# Smart_Humidifier.net
KiCad netlist of a schematic drawn in Altium Designer
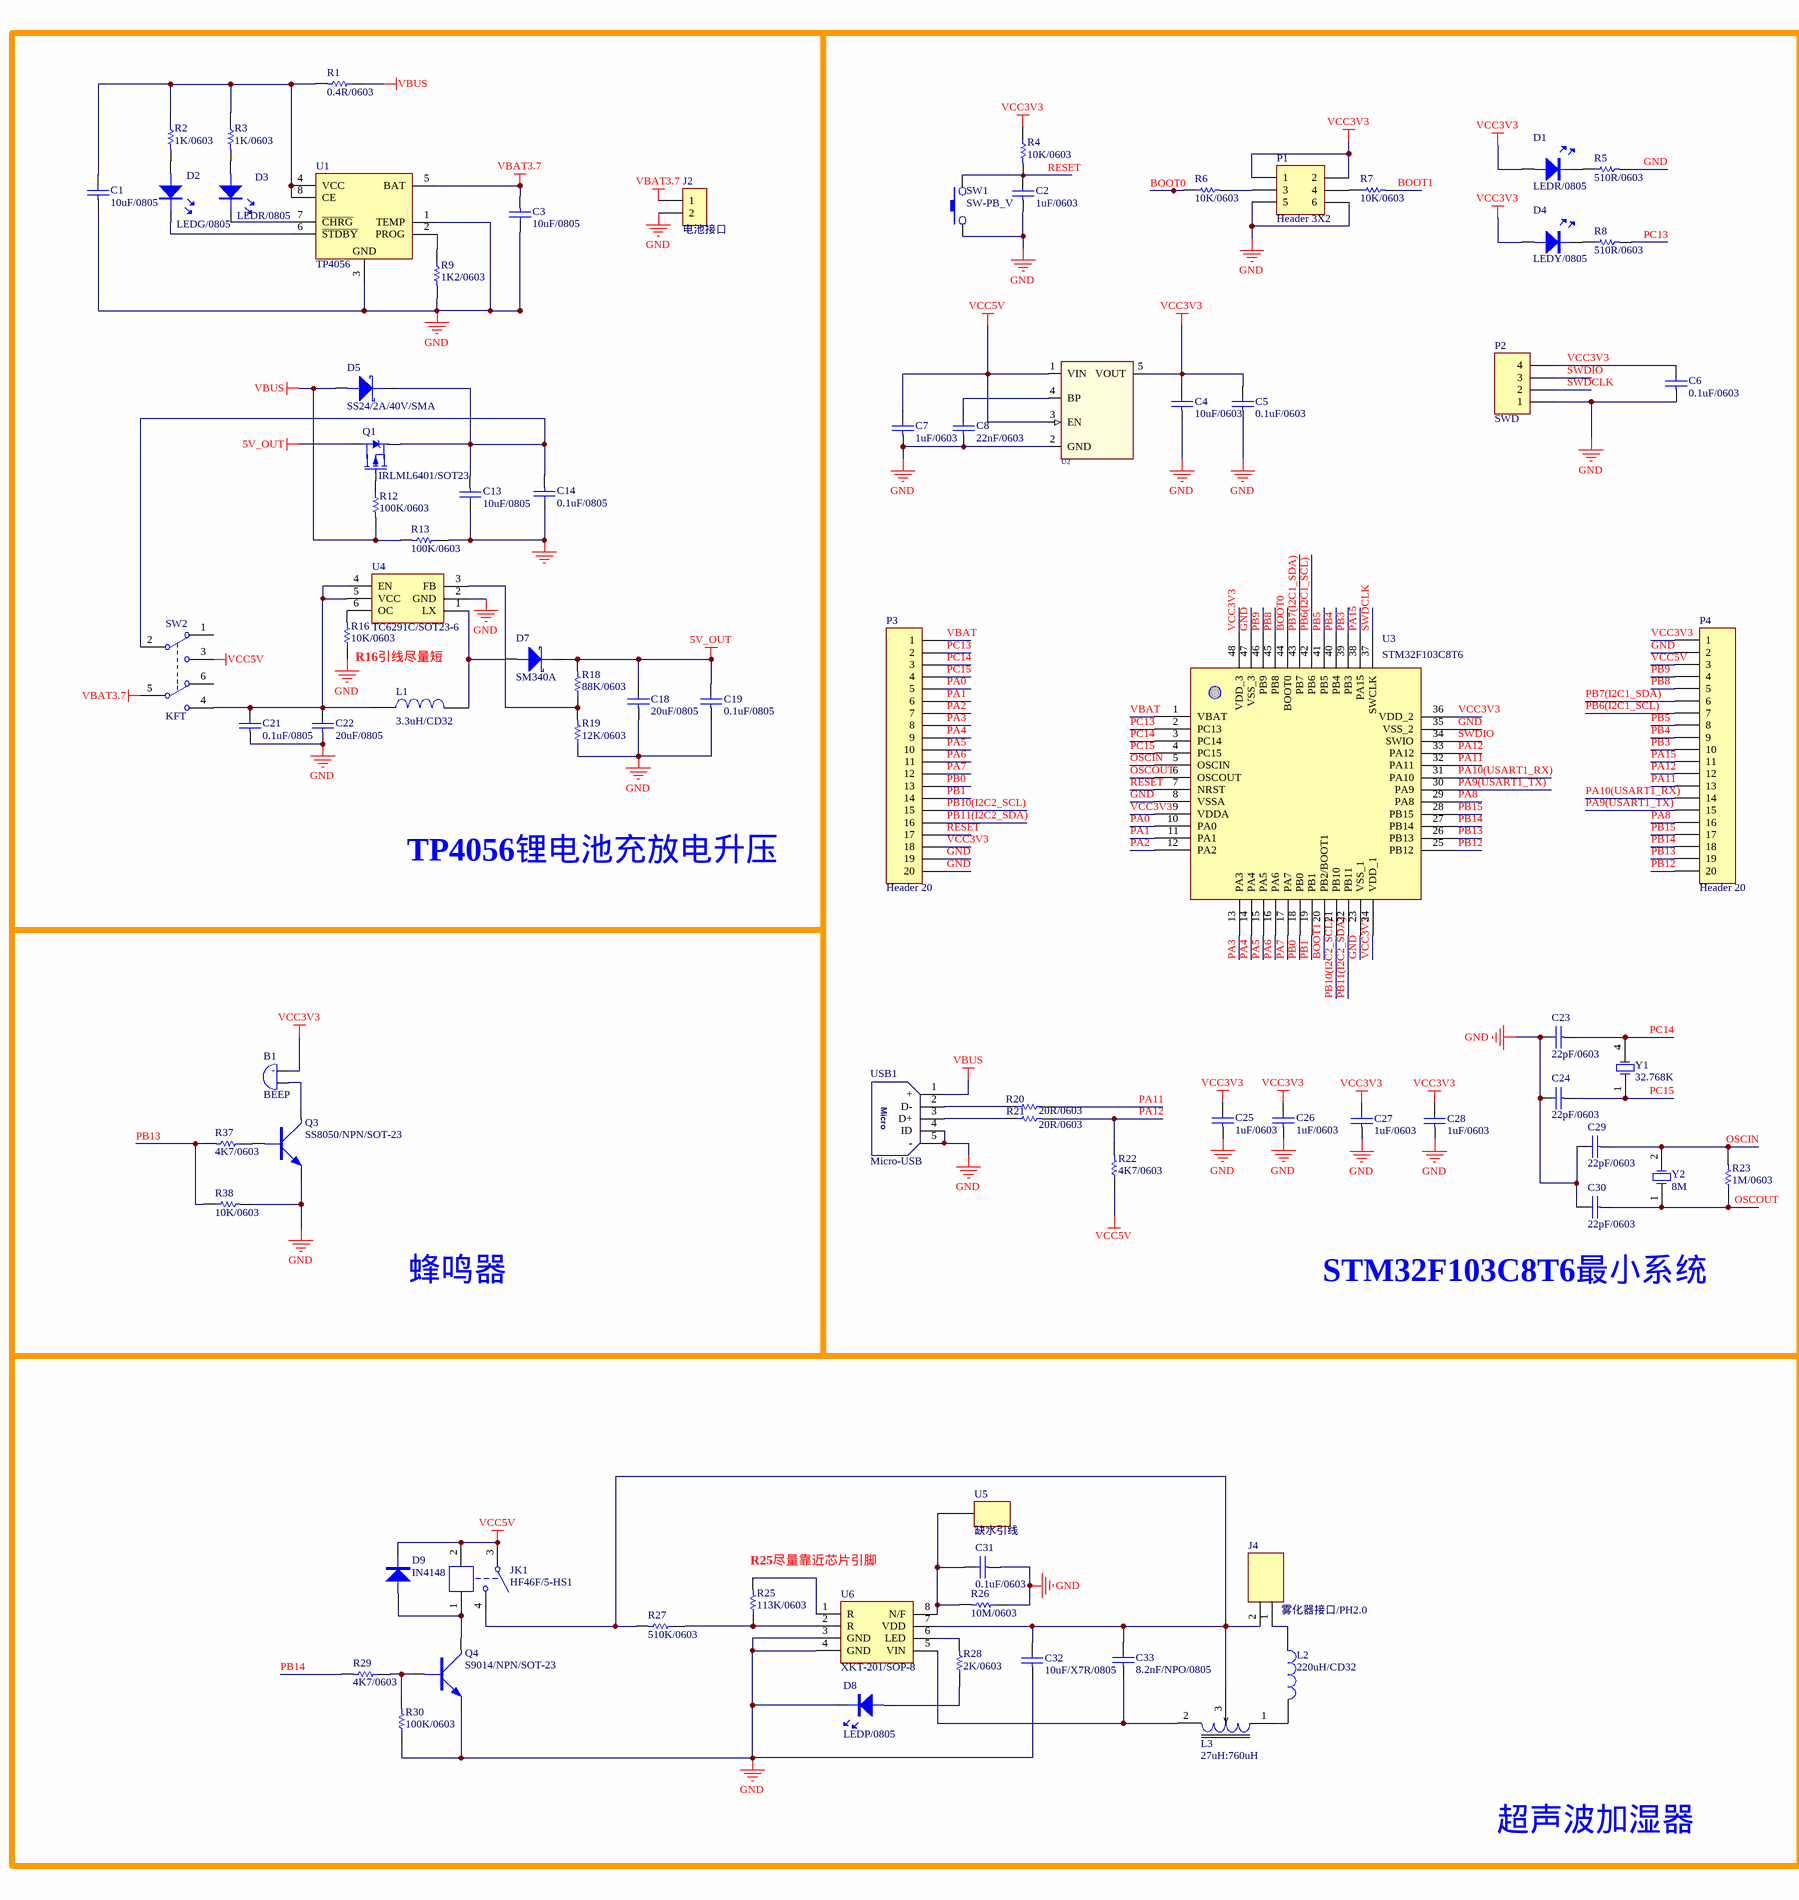
[diagram p0: Smart Humidifier.SchDoc, left]
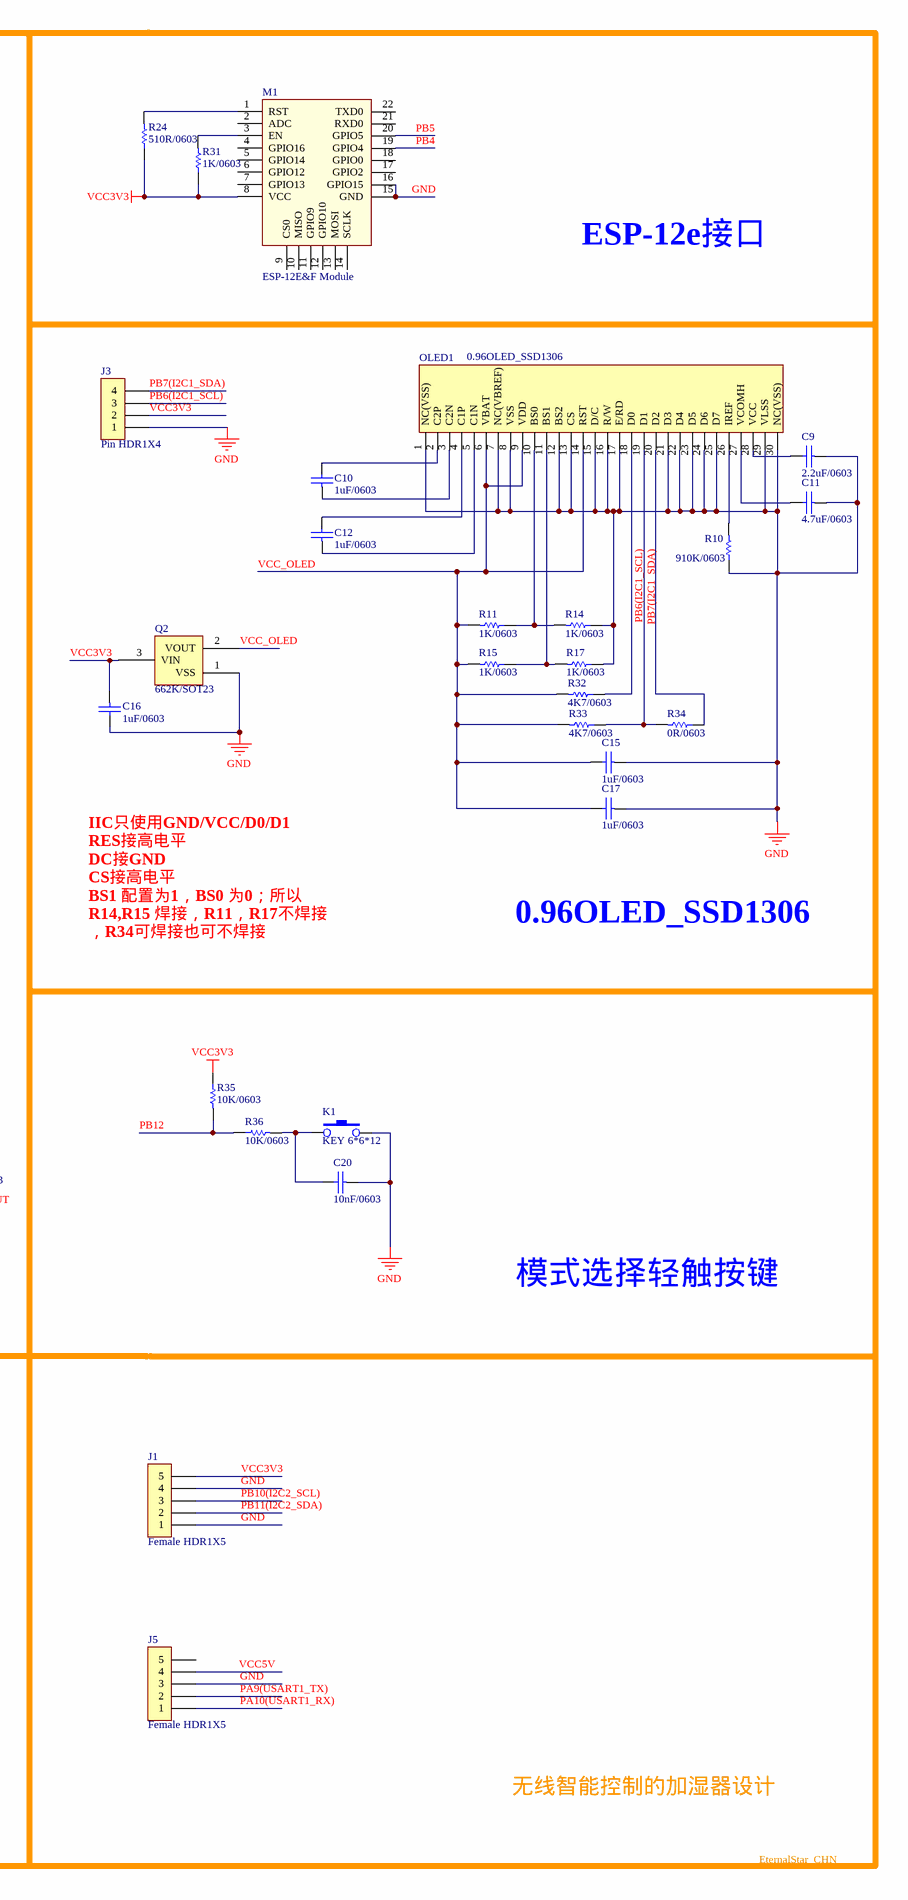
[diagram p1: Smart Humidifier.SchDoc, right]

(export (version "E")
  (design (tool "Eeschema 10.0.6"))
  (components
    (comp (ref "B1")
      (value "BEEP")
      (footprint "BEEP 5x9x5.5")
      (description "蜂鸣器")
      (libsource (lib "蜂鸣器") (part "BEEP"))
    )
    (comp (ref "C1")
      (value "10uF/0805")
      (footprint "0805C")
      (description "无极性电容")
      (libsource (lib "电容") (part "CAP"))
    )
    (comp (ref "C2")
      (value "1uF/0603")
      (footprint "0603C")
      (description "无极性电容")
      (libsource (lib "电容") (part "CAP"))
    )
    (comp (ref "C3")
      (value "10uF/0805")
      (footprint "0805C")
      (description "无极性电容")
      (libsource (lib "电容") (part "CAP"))
    )
    (comp (ref "C4")
      (value "10uF/0603")
      (footprint "0603C")
      (description "无极性电容")
      (libsource (lib "电容") (part "CAP"))
    )
    (comp (ref "C5")
      (value "0.1uF/0603")
      (footprint "0603C")
      (description "无极性电容")
      (libsource (lib "电容") (part "CAP"))
    )
    (comp (ref "C6")
      (value "0.1uF/0603")
      (footprint "0603C")
      (description "无极性电容")
      (libsource (lib "电容") (part "CAP"))
    )
    (comp (ref "C7")
      (value "1uF/0603")
      (footprint "0603C")
      (description "无极性电容")
      (libsource (lib "电容") (part "CAP"))
    )
    (comp (ref "C8")
      (value "22nF/0603")
      (footprint "0603C")
      (description "无极性电容")
      (libsource (lib "电容") (part "CAP"))
    )
    (comp (ref "C9")
      (value "2.2uF/0603")
      (footprint "0603C")
      (description "无极性电容")
      (libsource (lib "电容") (part "CAP"))
    )
    (comp (ref "C10")
      (value "1uF/0603")
      (footprint "0603C")
      (description "无极性电容")
      (libsource (lib "电容") (part "CAP"))
    )
    (comp (ref "C11")
      (value "4.7uF/0603")
      (footprint "0603C")
      (description "无极性电容")
      (libsource (lib "电容") (part "CAP"))
    )
    (comp (ref "C12")
      (value "1uF/0603")
      (footprint "0603C")
      (description "无极性电容")
      (libsource (lib "电容") (part "CAP"))
    )
    (comp (ref "C13")
      (value "10uF/0805")
      (footprint "0805C")
      (description "无极性电容")
      (libsource (lib "电容") (part "CAP"))
    )
    (comp (ref "C14")
      (value "0.1uF/0805")
      (footprint "0805C")
      (description "无极性电容")
      (libsource (lib "电容") (part "CAP"))
    )
    (comp (ref "C15")
      (value "1uF/0603")
      (footprint "0603C")
      (description "无极性电容")
      (libsource (lib "电容") (part "CAP"))
    )
    (comp (ref "C16")
      (value "1uF/0603")
      (footprint "0603C")
      (description "无极性电容")
      (libsource (lib "电容") (part "CAP"))
    )
    (comp (ref "C17")
      (value "1uF/0603")
      (footprint "0603C")
      (description "无极性电容")
      (libsource (lib "电容") (part "CAP"))
    )
    (comp (ref "C18")
      (value "20uF/0805")
      (footprint "0805C")
      (description "无极性电容")
      (libsource (lib "电容") (part "CAP"))
    )
    (comp (ref "C19")
      (value "0.1uF/0805")
      (footprint "0805C")
      (description "无极性电容")
      (libsource (lib "电容") (part "CAP"))
    )
    (comp (ref "C20")
      (value "10nF/0603")
      (footprint "0805C")
      (description "无极性电容")
      (libsource (lib "电容") (part "CAP"))
    )
    (comp (ref "C21")
      (value "0.1uF/0805")
      (footprint "0805C")
      (description "无极性电容")
      (libsource (lib "电容") (part "CAP"))
    )
    (comp (ref "C22")
      (value "20uF/0805")
      (footprint "0805C")
      (description "无极性电容")
      (libsource (lib "电容") (part "CAP"))
    )
    (comp (ref "C23")
      (value "22pF/0603")
      (footprint "0603C")
      (description "无极性电容")
      (libsource (lib "电容") (part "CAP"))
    )
    (comp (ref "C24")
      (value "22pF/0603")
      (footprint "0603C")
      (description "无极性电容")
      (libsource (lib "电容") (part "CAP"))
    )
    (comp (ref "C25")
      (value "1uF/0603")
      (footprint "0603C")
      (description "无极性电容")
      (libsource (lib "电容") (part "CAP"))
    )
    (comp (ref "C26")
      (value "1uF/0603")
      (footprint "0603C")
      (description "无极性电容")
      (libsource (lib "电容") (part "CAP"))
    )
    (comp (ref "C27")
      (value "1uF/0603")
      (footprint "0603C")
      (description "无极性电容")
      (libsource (lib "电容") (part "CAP"))
    )
    (comp (ref "C28")
      (value "1uF/0603")
      (footprint "0603C")
      (description "无极性电容")
      (libsource (lib "电容") (part "CAP"))
    )
    (comp (ref "C29")
      (value "22pF/0603")
      (footprint "0603C")
      (description "无极性电容")
      (libsource (lib "电容") (part "CAP"))
    )
    (comp (ref "C30")
      (value "22pF/0603")
      (footprint "0603C")
      (description "无极性电容")
      (libsource (lib "电容") (part "CAP"))
    )
    (comp (ref "C31")
      (value "0.1uF/0603")
      (footprint "0603C")
      (description "无极性电容")
      (libsource (lib "") (part "CAP_1"))
    )
    (comp (ref "C32")
      (value "10uF/X7R/0805")
      (footprint "0805C")
      (description "无极性电容")
      (libsource (lib "电容") (part "CAP"))
    )
    (comp (ref "C33")
      (value "8.2nF/NPO/0805")
      (footprint "0805C")
      (description "无极性电容")
      (libsource (lib "电容") (part "CAP"))
    )
    (comp (ref "D1") (value "LEDR/0805") (footprint "LED-0805R") (libsource (lib "LED") (part "LED")))
    (comp (ref "D2") (value "LEDG/0805") (footprint "LED-0805G") (libsource (lib "LED") (part "LED")))
    (comp (ref "D3") (value "LEDR/0805") (footprint "LED-0805R") (libsource (lib "LED") (part "LED")))
    (comp (ref "D4") (value "LEDY/0805") (footprint "LED-0805Y") (libsource (lib "LED") (part "LED")))
    (comp (ref "D5")
      (value "SS24/2A/40V/SMA")
      (footprint "SMA/DO-214AC")
      (description "肖特基二极管")
      (libsource (lib "二极管") (part "DIODE SCHOTTKY"))
    )
    (comp (ref "D7")
      (value "SM340A")
      (footprint "SMA/DO-214AC")
      (description "肖特基二极管")
      (libsource (lib "二极管") (part "DIODE SCHOTTKY"))
    )
    (comp (ref "D8") (value "LEDP/0805") (footprint "LED-0805Y") (libsource (lib "LED") (part "LED")))
    (comp (ref "D9")
      (value "IN4148")
      (footprint "SOD-523")
      (description "普通二极管")
      (libsource (lib "二极管") (part "DIODE"))
    )
    (comp (ref "J1")
      (value "Female HDR1X5")
      (footprint "Fe-HDR1X5/2.54-S")
      (libsource (lib "排母") (part "Female HDR1X5"))
    )
    (comp (ref "J2")
      (value "电池接口")
      (footprint "Fe-HDR1X2/2.54-S")
      (libsource (lib "排母") (part "Female HDR1X2"))
    )
    (comp (ref "J3")
      (value "Pin HDR1X4")
      (footprint "Pin HDR1X4/2.54mm-S")
      (libsource (lib "排针") (part "Pin HDR1X4"))
    )
    (comp (ref "J4") (value "雾化器接口/PH2.0") (footprint "PH2.0-2P") (libsource (lib "PH") (part "PH2.0-2P")))
    (comp (ref "J5")
      (value "Female HDR1X5")
      (footprint "Fe-HDR1X5/2.54-S")
      (libsource (lib "排母") (part "Female HDR1X5"))
    )
    (comp (ref "JK1")
      (value "HF46F/5-HS1")
      (footprint "HF46-xx-HS1")
      (description "5V一组常开")
      (fields (field (name "版权归属") "源创客"))
      (libsource (lib "继电器") (part "HF46F/5-HS1"))
    )
    (comp (ref "K1") (value "KEY 6*6*12") (footprint "DIP-6X6X12_C") (libsource (lib "轻触开关") (part "KEY")))
    (comp (ref "L1")
      (value "3.3uH/CD32")
      (footprint "CD32")
      (description "INDUCTOR")
      (libsource (lib "电感") (part "INDUCTOR"))
    )
    (comp (ref "L2")
      (value "220uH/CD32")
      (footprint "CD32")
      (description "INDUCTOR")
      (libsource (lib "Smart Humidifier") (part "INDUCTOR"))
    )
    (comp (ref "L3")
      (value "27uH:760uH")
      (footprint "INDUCTOR Tripod")
      (description "三脚工字形电感线圈直插式")
      (libsource (lib "Smart Humidifier") (part "INDUCTOR Tripod"))
    )
    (comp (ref "M1")
      (value "ESP-12E&F Module")
      (footprint "ESP-12E&F Module")
      (libsource (lib "ESP模块") (part "ESP-12E&F Module"))
    )
    (comp (ref "OLED1")
      (value "0.96OLED_SSD1306")
      (footprint "OLED_0.96")
      (libsource (lib "LCD") (part "0.96OLED_SSD1306"))
    )
    (comp (ref "P1")
      (value "Header 3X2")
      (footprint "HDR-3X2")
      (description "Header, 3-Pin, Dual row")
      (fields (field (name "PUBLISHER") "Altium Limited"))
      (libsource (lib "STM32F103C8T6") (part "Header 3X2"))
    )
    (comp (ref "P2")
      (value "SWD")
      (footprint "HDR-1X4_H")
      (description "Header, 4-Pin")
      (fields (field (name "PUBLISHER") "Altium Limited"))
      (libsource (lib "STM32F103C8T6") (part "Header 4"))
    )
    (comp (ref "P3")
      (value "Header 20")
      (footprint "HDR1X20")
      (description "Header, 20-Pin")
      (fields (field (name "PUBLISHER") "Altium Limited"))
      (libsource (lib "STM32F103C8T6") (part "Header 20"))
    )
    (comp (ref "P4")
      (value "Header 20")
      (footprint "HDR1X20")
      (description "Header, 20-Pin")
      (fields (field (name "PUBLISHER") "Altium Limited"))
      (libsource (lib "") (part "Header 20_1"))
    )
    (comp (ref "Q1")
      (value "IRLML6401/SOT23")
      (footprint "SOT23")
      (description "P沟道场效应管")
      (libsource (lib "MOS管") (part "P-MOS"))
    )
    (comp (ref "Q2")
      (value "662K/SOT23")
      (footprint "SOT23")
      (description "SOT23封装LDO")
      (libsource (lib "电源芯片") (part "LDO_SOT23"))
    )
    (comp (ref "Q3")
      (value "SS8050/NPN/SOT-23")
      (footprint "SOT-23")
      (description "NPN三极管")
      (libsource (lib "三极管") (part "NPN"))
    )
    (comp (ref "Q4")
      (value "S9014/NPN/SOT-23")
      (footprint "SOT-23")
      (description "NPN三极管")
      (libsource (lib "三极管") (part "NPN"))
    )
    (comp (ref "R1") (value "0.4R/0603") (footprint "0603R") (libsource (lib "电阻") (part "RES")))
    (comp (ref "R2") (value "1K/0603") (footprint "0603R") (libsource (lib "电阻") (part "RES")))
    (comp (ref "R3") (value "1K/0603") (footprint "0603R") (libsource (lib "电阻") (part "RES")))
    (comp (ref "R4") (value "10K/0603") (footprint "0603R") (libsource (lib "电阻") (part "RES")))
    (comp (ref "R5") (value "510R/0603") (footprint "0603R") (libsource (lib "电阻") (part "RES")))
    (comp (ref "R6") (value "10K/0603") (footprint "0603R") (libsource (lib "电阻") (part "RES")))
    (comp (ref "R7") (value "10K/0603") (footprint "0603R") (libsource (lib "电阻") (part "RES")))
    (comp (ref "R8") (value "510R/0603") (footprint "0603R") (libsource (lib "电阻") (part "RES")))
    (comp (ref "R9") (value "1K2/0603") (footprint "0603R") (libsource (lib "电阻") (part "RES")))
    (comp (ref "R10") (value "910K/0603") (footprint "0603R") (libsource (lib "电阻") (part "RES")))
    (comp (ref "R11") (value "1K/0603") (footprint "0603R") (libsource (lib "电阻") (part "RES")))
    (comp (ref "R12") (value "100K/0603") (footprint "0603R") (libsource (lib "电阻") (part "RES")))
    (comp (ref "R13") (value "100K/0603") (footprint "0603R") (libsource (lib "电阻") (part "RES")))
    (comp (ref "R14") (value "1K/0603") (footprint "0603R") (libsource (lib "电阻") (part "RES")))
    (comp (ref "R15") (value "1K/0603") (footprint "0603R") (libsource (lib "电阻") (part "RES")))
    (comp (ref "R16") (value "10K/0603") (footprint "0603R") (libsource (lib "电阻") (part "RES")))
    (comp (ref "R17") (value "1K/0603") (footprint "0603R") (libsource (lib "电阻") (part "RES")))
    (comp (ref "R18") (value "88K/0603") (footprint "0603R") (libsource (lib "电阻") (part "RES")))
    (comp (ref "R19") (value "12K/0603") (footprint "0603R") (libsource (lib "电阻") (part "RES")))
    (comp (ref "R20") (value "20R/0603") (footprint "0603R") (libsource (lib "电阻") (part "RES")))
    (comp (ref "R21") (value "20R/0603") (footprint "0603R") (libsource (lib "电阻") (part "RES")))
    (comp (ref "R22") (value "4K7/0603") (footprint "0603R") (libsource (lib "电阻") (part "RES")))
    (comp (ref "R23") (value "1M/0603") (footprint "0603R") (libsource (lib "电阻") (part "RES")))
    (comp (ref "R24") (value "510R/0603") (footprint "0603R") (libsource (lib "电阻") (part "RES")))
    (comp (ref "R25") (value "113K/0603") (footprint "0603R") (libsource (lib "电阻") (part "RES")))
    (comp (ref "R26") (value "10M/0603") (footprint "0603R") (libsource (lib "电阻") (part "RES")))
    (comp (ref "R27") (value "510K/0603") (footprint "0603R") (libsource (lib "电阻") (part "RES")))
    (comp (ref "R28") (value "2K/0603") (footprint "0603R") (libsource (lib "电阻") (part "RES")))
    (comp (ref "R29") (value "4K7/0603") (footprint "0603R") (libsource (lib "电阻") (part "RES")))
    (comp (ref "R30") (value "100K/0603") (footprint "0603R") (libsource (lib "电阻") (part "RES")))
    (comp (ref "R31") (value "1K/0603") (footprint "0603R") (libsource (lib "电阻") (part "RES")))
    (comp (ref "R32") (value "4K7/0603") (footprint "0603R") (libsource (lib "电阻") (part "RES")))
    (comp (ref "R33") (value "4K7/0603") (footprint "0603R") (libsource (lib "电阻") (part "RES")))
    (comp (ref "R34") (value "0R/0603") (footprint "0603R") (libsource (lib "电阻") (part "RES")))
    (comp (ref "R35") (value "10K/0603") (footprint "0603R") (libsource (lib "电阻") (part "RES")))
    (comp (ref "R36") (value "10K/0603") (footprint "0603R") (libsource (lib "电阻") (part "RES")))
    (comp (ref "R37") (value "4K7/0603") (footprint "0603R") (libsource (lib "电阻") (part "RES")))
    (comp (ref "R38") (value "10K/0603") (footprint "0603R") (libsource (lib "电阻") (part "RES")))
    (comp (ref "SW1")
      (value "SW-PB_V")
      (footprint "TSW SMD-3*6*2.5")
      (description "SWITCH")
      (libsource (lib "STM32F103C8T6") (part "SW-PB_V"))
    )
    (comp (ref "SW2")
      (value "KFT")
      (footprint "KFT DIP-7X7")
      (description "Self-locking Switch")
      (libsource (lib "Smart Humidifier") (part "KFT_7X7-DIP"))
    )
    (comp (ref "U1") (value "TP4056") (footprint "SOP8") (libsource (lib "电源芯片") (part "TP4056")))
    (comp (ref "U2")
      (value "RT9193")
      (footprint "SOT23-5L")
      (fields (field (name "ICA_PARTNUM") "$$2191094$$RT9193-15CU5") (field (name "PART NUMBER") "TMP-13"))
      (libsource (lib "STM32F103C8T6") (part "RT9193X_5P"))
    )
    (comp (ref "U3")
      (value "STM32F103C8T6")
      (footprint "TQFP48 7x7_L")
      (libsource (lib "STM32F103C8T6") (part "STM32F103C8T6"))
    )
    (comp (ref "U4")
      (value "TC6291C/SOT23-6")
      (footprint "SOT23-6")
      (description "DC-DC升压IC")
      (libsource (lib "Li_Test") (part "TC6291C"))
    )
    (comp (ref "U5") (value "缺水引线") (footprint "通孔焊盘") (libsource (lib "Smart Humidifier") (part "过孔焊盘")))
    (comp (ref "U6")
      (value "XKT-201/SOP-8")
      (footprint "SOP8")
      (description "5V加湿器驱动芯片")
      (libsource (lib "Smart Humidifier") (part "XKT-201"))
    )
    (comp (ref "USB1")
      (value "Micro-USB")
      (footprint "USB-micro_B")
      (libsource (lib "USB") (part "Micro-USB"))
    )
    (comp (ref "Y1")
      (value "32.768K")
      (footprint "MC-306")
      (description "Crystal Oscillator")
      (fields (field (name "PUBLISHER") "Altium Limited"))
      (libsource (lib "") (part "XTAL_1"))
    )
    (comp (ref "Y2")
      (value "8M")
      (footprint "XTAL-49S DIP")
      (description "Crystal Oscillator")
      (fields (field (name "PUBLISHER") "Altium Limited"))
      (libsource (lib "STM32F103C8T6") (part "XTAL"))
    )
  )
  (nets
    (net (code "1") (name "/BOOT0") (class "Default")
      (node (ref "R6") (pin "1") (pinfunction "1_1") (pintype "passive"))
      (node (ref "U3") (pin "44") (pinfunction "BOOT0_44") (pintype "passive"))
    )
    (net (code "2") (name "/BOOT1") (class "Default")
      (node (ref "R7") (pin "2") (pinfunction "2_2") (pintype "passive"))
      (node (ref "U3") (pin "20") (pinfunction "PB2/BOOT1_20") (pintype "passive"))
    )
    (net (code "3") (name "/OSCIN") (class "Default")
      (node (ref "C29") (pin "1") (pinfunction "1_1") (pintype "passive"))
      (node (ref "R23") (pin "2") (pinfunction "2_2") (pintype "passive"))
      (node (ref "U3") (pin "5") (pinfunction "OSCIN_5") (pintype "passive"))
      (node (ref "Y2") (pin "2") (pinfunction "OSC2_2") (pintype "passive"))
    )
    (net (code "4") (name "/OSCOUT") (class "Default")
      (node (ref "C30") (pin "1") (pinfunction "1_1") (pintype "passive"))
      (node (ref "R23") (pin "1") (pinfunction "1_1") (pintype "passive"))
      (node (ref "U3") (pin "6") (pinfunction "OSCOUT_6") (pintype "passive"))
      (node (ref "Y2") (pin "1") (pinfunction "OSC1_1") (pintype "passive"))
    )
    (net (code "5") (name "/PA0") (class "Default")
      (node (ref "P3") (pin "5") (pinfunction "5_5") (pintype "passive"))
      (node (ref "U3") (pin "10") (pinfunction "PA0_10") (pintype "passive"))
    )
    (net (code "6") (name "/PA1") (class "Default")
      (node (ref "P3") (pin "6") (pinfunction "6_6") (pintype "passive"))
      (node (ref "U3") (pin "11") (pinfunction "PA1_11") (pintype "passive"))
    )
    (net (code "7") (name "/PA2") (class "Default")
      (node (ref "P3") (pin "7") (pinfunction "7_7") (pintype "passive"))
      (node (ref "U3") (pin "12") (pinfunction "PA2_12") (pintype "passive"))
    )
    (net (code "8") (name "/PA3") (class "Default")
      (node (ref "P3") (pin "8") (pinfunction "8_8") (pintype "passive"))
      (node (ref "U3") (pin "13") (pinfunction "PA3_13") (pintype "passive"))
    )
    (net (code "9") (name "/PA4") (class "Default")
      (node (ref "P3") (pin "9") (pinfunction "9_9") (pintype "passive"))
      (node (ref "U3") (pin "14") (pinfunction "PA4_14") (pintype "passive"))
    )
    (net (code "10") (name "/PA5") (class "Default")
      (node (ref "P3") (pin "10") (pinfunction "10_10") (pintype "passive"))
      (node (ref "U3") (pin "15") (pinfunction "PA5_15") (pintype "passive"))
    )
    (net (code "11") (name "/PA6") (class "Default")
      (node (ref "P3") (pin "11") (pinfunction "11_11") (pintype "passive"))
      (node (ref "U3") (pin "16") (pinfunction "PA6_16") (pintype "passive"))
    )
    (net (code "12") (name "/PA7") (class "Default")
      (node (ref "P3") (pin "12") (pinfunction "12_12") (pintype "passive"))
      (node (ref "U3") (pin "17") (pinfunction "PA7_17") (pintype "passive"))
    )
    (net (code "13") (name "/PA8") (class "Default")
      (node (ref "P4") (pin "16") (pinfunction "16_16") (pintype "passive"))
      (node (ref "U3") (pin "29") (pinfunction "PA8_29") (pintype "passive"))
    )
    (net (code "14") (name "/PA9(USART1_TX)") (class "Default")
      (node (ref "J5") (pin "2") (pinfunction "2_2") (pintype "passive"))
      (node (ref "P4") (pin "15") (pinfunction "15_15") (pintype "passive"))
      (node (ref "U3") (pin "30") (pinfunction "PA9_30") (pintype "passive"))
    )
    (net (code "15") (name "/PA10(USART1_RX)") (class "Default")
      (node (ref "J5") (pin "1") (pinfunction "1_1") (pintype "passive"))
      (node (ref "P4") (pin "14") (pinfunction "14_14") (pintype "passive"))
      (node (ref "U3") (pin "31") (pinfunction "PA10_31") (pintype "passive"))
    )
    (net (code "16") (name "/PA11") (class "Default")
      (node (ref "P4") (pin "13") (pinfunction "13_13") (pintype "passive"))
      (node (ref "R20") (pin "2") (pinfunction "2_2") (pintype "passive"))
      (node (ref "U3") (pin "32") (pinfunction "PA11_32") (pintype "passive"))
    )
    (net (code "17") (name "/PA12") (class "Default")
      (node (ref "P4") (pin "12") (pinfunction "12_12") (pintype "passive"))
      (node (ref "R21") (pin "2") (pinfunction "2_2") (pintype "passive"))
      (node (ref "R22") (pin "2") (pinfunction "2_2") (pintype "passive"))
      (node (ref "U3") (pin "33") (pinfunction "PA12_33") (pintype "passive"))
    )
    (net (code "18") (name "/PA15") (class "Default")
      (node (ref "P4") (pin "11") (pinfunction "11_11") (pintype "passive"))
      (node (ref "U3") (pin "38") (pinfunction "PA15_38") (pintype "passive"))
    )
    (net (code "19") (name "/PB0") (class "Default")
      (node (ref "P3") (pin "13") (pinfunction "13_13") (pintype "passive"))
      (node (ref "U3") (pin "18") (pinfunction "PB0_18") (pintype "passive"))
    )
    (net (code "20") (name "/PB1") (class "Default")
      (node (ref "P3") (pin "14") (pinfunction "14_14") (pintype "passive"))
      (node (ref "U3") (pin "19") (pinfunction "PB1_19") (pintype "passive"))
    )
    (net (code "21") (name "/PB3") (class "Default")
      (node (ref "P4") (pin "10") (pinfunction "10_10") (pintype "passive"))
      (node (ref "U3") (pin "39") (pinfunction "PB3_39") (pintype "passive"))
    )
    (net (code "22") (name "/PB4") (class "Default")
      (node (ref "M1") (pin "19") (pinfunction "GPIO4_19") (pintype "passive"))
      (node (ref "P4") (pin "9") (pinfunction "9_9") (pintype "passive"))
      (node (ref "U3") (pin "40") (pinfunction "PB4_40") (pintype "passive"))
    )
    (net (code "23") (name "/PB5") (class "Default")
      (node (ref "M1") (pin "20") (pinfunction "GPIO5_20") (pintype "passive"))
      (node (ref "P4") (pin "8") (pinfunction "8_8") (pintype "passive"))
      (node (ref "U3") (pin "41") (pinfunction "PB5_41") (pintype "passive"))
    )
    (net (code "24") (name "/PB6(I2C1_SCL)") (class "Default")
      (node (ref "J3") (pin "3") (pinfunction "3_3") (pintype "passive"))
      (node (ref "OLED1") (pin "18") (pinfunction "D0_18") (pintype "passive"))
      (node (ref "P4") (pin "7") (pinfunction "7_7") (pintype "passive"))
      (node (ref "R32") (pin "1") (pinfunction "1_1") (pintype "passive"))
      (node (ref "U3") (pin "42") (pinfunction "PB6_42") (pintype "passive"))
    )
    (net (code "25") (name "/PB7(I2C1_SDA)") (class "Default")
      (node (ref "J3") (pin "4") (pinfunction "4_4") (pintype "passive"))
      (node (ref "OLED1") (pin "19") (pinfunction "D1_19") (pintype "passive"))
      (node (ref "P4") (pin "6") (pinfunction "6_6") (pintype "passive"))
      (node (ref "R33") (pin "1") (pinfunction "1_1") (pintype "passive"))
      (node (ref "R34") (pin "2") (pinfunction "2_2") (pintype "passive"))
      (node (ref "U3") (pin "43") (pinfunction "PB7_43") (pintype "passive"))
    )
    (net (code "26") (name "/PB8") (class "Default")
      (node (ref "P4") (pin "5") (pinfunction "5_5") (pintype "passive"))
      (node (ref "U3") (pin "45") (pinfunction "PB8_45") (pintype "passive"))
    )
    (net (code "27") (name "/PB9") (class "Default")
      (node (ref "P4") (pin "4") (pinfunction "4_4") (pintype "passive"))
      (node (ref "U3") (pin "46") (pinfunction "PB9_46") (pintype "passive"))
    )
    (net (code "28") (name "/PB10(I2C2_SCL)") (class "Default")
      (node (ref "J1") (pin "3") (pinfunction "3_3") (pintype "passive"))
      (node (ref "P3") (pin "15") (pinfunction "15_15") (pintype "passive"))
      (node (ref "U3") (pin "21") (pinfunction "PB10_21") (pintype "passive"))
    )
    (net (code "29") (name "/PB11(I2C2_SDA)") (class "Default")
      (node (ref "J1") (pin "2") (pinfunction "2_2") (pintype "passive"))
      (node (ref "P3") (pin "16") (pinfunction "16_16") (pintype "passive"))
      (node (ref "U3") (pin "22") (pinfunction "PB11_22") (pintype "passive"))
    )
    (net (code "30") (name "/PB12") (class "Default")
      (node (ref "P4") (pin "20") (pinfunction "20_20") (pintype "passive"))
      (node (ref "R35") (pin "2") (pinfunction "2_2") (pintype "passive"))
      (node (ref "R36") (pin "1") (pinfunction "1_1") (pintype "passive"))
      (node (ref "U3") (pin "25") (pinfunction "PB12_25") (pintype "passive"))
    )
    (net (code "31") (name "/PB13") (class "Default")
      (node (ref "P4") (pin "19") (pinfunction "19_19") (pintype "passive"))
      (node (ref "R37") (pin "2") (pinfunction "2_2") (pintype "passive"))
      (node (ref "R38") (pin "1") (pinfunction "1_1") (pintype "passive"))
      (node (ref "U3") (pin "26") (pinfunction "PB13_26") (pintype "passive"))
    )
    (net (code "32") (name "/PB14") (class "Default")
      (node (ref "P4") (pin "18") (pinfunction "18_18") (pintype "passive"))
      (node (ref "R29") (pin "2") (pinfunction "2_2") (pintype "passive"))
      (node (ref "U3") (pin "27") (pinfunction "PB14_27") (pintype "passive"))
    )
    (net (code "33") (name "/PB15") (class "Default")
      (node (ref "P4") (pin "17") (pinfunction "17_17") (pintype "passive"))
      (node (ref "U3") (pin "28") (pinfunction "PB15_28") (pintype "passive"))
    )
    (net (code "34") (name "/PC13") (class "Default")
      (node (ref "P3") (pin "2") (pinfunction "2_2") (pintype "passive"))
      (node (ref "R8") (pin "2") (pinfunction "2_2") (pintype "passive"))
      (node (ref "U3") (pin "2") (pinfunction "PC13_2") (pintype "passive"))
    )
    (net (code "35") (name "/PC14") (class "Default")
      (node (ref "C23") (pin "1") (pinfunction "1_1") (pintype "passive"))
      (node (ref "P3") (pin "3") (pinfunction "3_3") (pintype "passive"))
      (node (ref "U3") (pin "3") (pinfunction "PC14_3") (pintype "passive"))
      (node (ref "Y1") (pin "4") (pinfunction "OSC2_4") (pintype "passive"))
    )
    (net (code "36") (name "/PC15") (class "Default")
      (node (ref "C24") (pin "1") (pinfunction "1_1") (pintype "passive"))
      (node (ref "P3") (pin "4") (pinfunction "4_4") (pintype "passive"))
      (node (ref "U3") (pin "4") (pinfunction "PC15_4") (pintype "passive"))
      (node (ref "Y1") (pin "1") (pinfunction "OSC1_1") (pintype "passive"))
    )
    (net (code "37") (name "/RESET") (class "Default")
      (node (ref "C2") (pin "2") (pinfunction "2_2") (pintype "passive"))
      (node (ref "P3") (pin "17") (pinfunction "17_17") (pintype "passive"))
      (node (ref "R4") (pin "2") (pinfunction "2_2") (pintype "passive"))
      (node (ref "SW1") (pin "2") (pinfunction "2_2") (pintype "passive"))
      (node (ref "U3") (pin "7") (pinfunction "NRST_7") (pintype "passive"))
    )
    (net (code "38") (name "/SWDCLK") (class "Default")
      (node (ref "P2") (pin "2") (pinfunction "2_2") (pintype "passive"))
      (node (ref "U3") (pin "37") (pinfunction "SWCLK_37") (pintype "passive"))
    )
    (net (code "39") (name "/SWDIO") (class "Default")
      (node (ref "P2") (pin "3") (pinfunction "3_3") (pintype "passive"))
      (node (ref "U3") (pin "34") (pinfunction "SWIO_34") (pintype "passive"))
    )
    (net (code "40") (name "/VBAT") (class "Default")
      (node (ref "P3") (pin "1") (pinfunction "1_1") (pintype "passive"))
      (node (ref "U3") (pin "1") (pinfunction "VBAT_1") (pintype "passive"))
    )
    (net (code "41") (name "/VCC_OLED") (class "Default")
      (node (ref "C15") (pin "2") (pinfunction "2_2") (pintype "passive"))
      (node (ref "C17") (pin "2") (pinfunction "2_2") (pintype "passive"))
      (node (ref "OLED1") (pin "14") (pinfunction "RST_14") (pintype "passive"))
      (node (ref "OLED1") (pin "6") (pinfunction "VBAT_6") (pintype "passive"))
      (node (ref "OLED1") (pin "9") (pinfunction "VDD_9") (pintype "passive"))
      (node (ref "Q2") (pin "2") (pinfunction "VOUT_2") (pintype "passive"))
      (node (ref "R11") (pin "2") (pinfunction "2_2") (pintype "passive"))
      (node (ref "R15") (pin "2") (pinfunction "2_2") (pintype "passive"))
      (node (ref "R32") (pin "2") (pinfunction "2_2") (pintype "passive"))
      (node (ref "R33") (pin "2") (pinfunction "2_2") (pintype "passive"))
    )
    (net (code "42") (name "5V_OUT") (class "Default")
      (node (ref "C18") (pin "2") (pinfunction "2_2") (pintype "passive"))
      (node (ref "C19") (pin "2") (pinfunction "2_2") (pintype "passive"))
      (node (ref "D7") (pin "K") (pinfunction "K_K") (pintype "passive"))
      (node (ref "Q1") (pin "D") (pinfunction "D_D") (pintype "passive"))
      (node (ref "R18") (pin "2") (pinfunction "2_2") (pintype "passive"))
    )
    (net (code "43") (name "GND") (class "Default")
      (node (ref "C1") (pin "1") (pinfunction "1_1") (pintype "passive"))
      (node (ref "C11") (pin "1") (pinfunction "1_1") (pintype "passive"))
      (node (ref "C13") (pin "2") (pinfunction "2_2") (pintype "passive"))
      (node (ref "C14") (pin "2") (pinfunction "2_2") (pintype "passive"))
      (node (ref "C15") (pin "1") (pinfunction "1_1") (pintype "passive"))
      (node (ref "C16") (pin "2") (pinfunction "2_2") (pintype "passive"))
      (node (ref "C17") (pin "1") (pinfunction "1_1") (pintype "passive"))
      (node (ref "C18") (pin "1") (pinfunction "1_1") (pintype "passive"))
      (node (ref "C19") (pin "1") (pinfunction "1_1") (pintype "passive"))
      (node (ref "C2") (pin "1") (pinfunction "1_1") (pintype "passive"))
      (node (ref "C20") (pin "1") (pinfunction "1_1") (pintype "passive"))
      (node (ref "C21") (pin "1") (pinfunction "1_1") (pintype "passive"))
      (node (ref "C22") (pin "1") (pinfunction "1_1") (pintype "passive"))
      (node (ref "C23") (pin "2") (pinfunction "2_2") (pintype "passive"))
      (node (ref "C24") (pin "2") (pinfunction "2_2") (pintype "passive"))
      (node (ref "C25") (pin "1") (pinfunction "1_1") (pintype "passive"))
      (node (ref "C26") (pin "1") (pinfunction "1_1") (pintype "passive"))
      (node (ref "C27") (pin "1") (pinfunction "1_1") (pintype "passive"))
      (node (ref "C28") (pin "1") (pinfunction "1_1") (pintype "passive"))
      (node (ref "C29") (pin "2") (pinfunction "2_2") (pintype "passive"))
      (node (ref "C3") (pin "2") (pinfunction "2_2") (pintype "passive"))
      (node (ref "C30") (pin "2") (pinfunction "2_2") (pintype "passive"))
      (node (ref "C31") (pin "2") (pinfunction "2_2") (pintype "passive"))
      (node (ref "C32") (pin "1") (pinfunction "1_1") (pintype "passive"))
      (node (ref "C4") (pin "1") (pinfunction "1_1") (pintype "passive"))
      (node (ref "C5") (pin "1") (pinfunction "1_1") (pintype "passive"))
      (node (ref "C6") (pin "1") (pinfunction "1_1") (pintype "passive"))
      (node (ref "C7") (pin "1") (pinfunction "1_1") (pintype "passive"))
      (node (ref "C8") (pin "1") (pinfunction "1_1") (pintype "passive"))
      (node (ref "C9") (pin "1") (pinfunction "1_1") (pintype "passive"))
      (node (ref "D8") (pin "K") (pinfunction "K_K") (pintype "passive"))
      (node (ref "J1") (pin "1") (pinfunction "1_1") (pintype "passive"))
      (node (ref "J1") (pin "4") (pinfunction "4_4") (pintype "passive"))
      (node (ref "J2") (pin "2") (pinfunction "2_2") (pintype "passive"))
      (node (ref "J3") (pin "1") (pinfunction "1_1") (pintype "passive"))
      (node (ref "J5") (pin "3") (pinfunction "3_3") (pintype "passive"))
      (node (ref "K1") (pin "3") (pinfunction "3_3") (pintype "passive"))
      (node (ref "M1") (pin "15") (pinfunction "GND_15") (pintype "passive"))
      (node (ref "M1") (pin "16") (pinfunction "GPIO15_16") (pintype "passive"))
      (node (ref "OLED1") (pin "1") (pinfunction "NC(VSS)_1") (pintype "passive"))
      (node (ref "OLED1") (pin "12") (pinfunction "BS2_12") (pintype "passive"))
      (node (ref "OLED1") (pin "13") (pinfunction "CS_13") (pintype "passive"))
      (node (ref "OLED1") (pin "15") (pinfunction "D/C_15") (pintype "passive"))
      (node (ref "OLED1") (pin "16") (pinfunction "R/W_16") (pintype "passive"))
      (node (ref "OLED1") (pin "17") (pinfunction "E/RD_17") (pintype "passive"))
      (node (ref "OLED1") (pin "21") (pinfunction "D3_21") (pintype "passive"))
      (node (ref "OLED1") (pin "22") (pinfunction "D4_22") (pintype "passive"))
      (node (ref "OLED1") (pin "23") (pinfunction "D5_23") (pintype "passive"))
      (node (ref "OLED1") (pin "24") (pinfunction "D6_24") (pintype "passive"))
      (node (ref "OLED1") (pin "25") (pinfunction "D7_25") (pintype "passive"))
      (node (ref "OLED1") (pin "29") (pinfunction "VLSS_29") (pintype "passive"))
      (node (ref "OLED1") (pin "30") (pinfunction "NC(VSS)_30") (pintype "passive"))
      (node (ref "OLED1") (pin "7") (pinfunction "NC(VBREF)_7") (pintype "passive"))
      (node (ref "OLED1") (pin "8") (pinfunction "VSS_8") (pintype "passive"))
      (node (ref "P1") (pin "5") (pinfunction "5_5") (pintype "passive"))
      (node (ref "P1") (pin "6") (pinfunction "6_6") (pintype "passive"))
      (node (ref "P2") (pin "1") (pinfunction "1_1") (pintype "passive"))
      (node (ref "P3") (pin "19") (pinfunction "19_19") (pintype "passive"))
      (node (ref "P3") (pin "20") (pinfunction "20_20") (pintype "passive"))
      (node (ref "P4") (pin "2") (pinfunction "2_2") (pintype "passive"))
      (node (ref "Q2") (pin "1") (pinfunction "VSS_1") (pintype "passive"))
      (node (ref "Q3") (pin "E") (pinfunction "E_E") (pintype "passive"))
      (node (ref "Q4") (pin "E") (pinfunction "E_E") (pintype "passive"))
      (node (ref "R10") (pin "1") (pinfunction "1_1") (pintype "passive"))
      (node (ref "R13") (pin "1") (pinfunction "1_1") (pintype "passive"))
      (node (ref "R14") (pin "1") (pinfunction "1_1") (pintype "passive"))
      (node (ref "R16") (pin "1") (pinfunction "1_1") (pintype "passive"))
      (node (ref "R17") (pin "1") (pinfunction "1_1") (pintype "passive"))
      (node (ref "R19") (pin "1") (pinfunction "1_1") (pintype "passive"))
      (node (ref "R26") (pin "1") (pinfunction "1_1") (pintype "passive"))
      (node (ref "R30") (pin "1") (pinfunction "1_1") (pintype "passive"))
      (node (ref "R38") (pin "2") (pinfunction "2_2") (pintype "passive"))
      (node (ref "R5") (pin "2") (pinfunction "2_2") (pintype "passive"))
      (node (ref "R9") (pin "2") (pinfunction "2_2") (pintype "passive"))
      (node (ref "SW1") (pin "1") (pinfunction "1_1") (pintype "passive"))
      (node (ref "U1") (pin "1") (pinfunction "TEMP_1") (pintype "passive"))
      (node (ref "U1") (pin "3") (pinfunction "GND_3") (pintype "passive"))
      (node (ref "U2") (pin "2") (pinfunction "GND_2") (pintype "power_in"))
      (node (ref "U3") (pin "23") (pinfunction "VSS_1_23") (pintype "passive"))
      (node (ref "U3") (pin "35") (pinfunction "VSS_2_35") (pintype "passive"))
      (node (ref "U3") (pin "47") (pinfunction "VSS_3_47") (pintype "passive"))
      (node (ref "U3") (pin "8") (pinfunction "VSSA_8") (pintype "passive"))
      (node (ref "U4") (pin "2") (pinfunction "GND_2") (pintype "passive"))
      (node (ref "U6") (pin "3") (pinfunction "GND_3") (pintype "passive"))
      (node (ref "U6") (pin "4") (pinfunction "GND_4") (pintype "passive"))
      (node (ref "USB1") (pin "4") (pinfunction "ID_4") (pintype "passive"))
      (node (ref "USB1") (pin "5") (pinfunction "-_5") (pintype "passive"))
    )
    (net (code "44") (name "Net-(B1-Pad2)") (class "Default")
      (node (ref "B1") (pin "2") (pinfunction "2_2") (pintype "passive"))
      (node (ref "Q3") (pin "C") (pinfunction "C_C") (pintype "passive"))
    )
    (net (code "45") (name "Net-(C13-Pad1)") (class "Default")
      (node (ref "C13") (pin "1") (pinfunction "1_1") (pintype "passive"))
      (node (ref "C14") (pin "1") (pinfunction "1_1") (pintype "passive"))
      (node (ref "D5") (pin "K") (pinfunction "K_K") (pintype "passive"))
      (node (ref "Q1") (pin "S") (pinfunction "S_S") (pintype "passive"))
      (node (ref "SW2") (pin "2") (pinfunction "COM2_2") (pintype "passive"))
    )
    (net (code "46") (name "Net-(C20-Pad2)") (class "Default")
      (node (ref "C20") (pin "2") (pinfunction "2_2") (pintype "passive"))
      (node (ref "K1") (pin "1") (pinfunction "1_1") (pintype "passive"))
      (node (ref "R36") (pin "2") (pinfunction "2_2") (pintype "passive"))
    )
    (net (code "47") (name "Net-(D1-PadK)") (class "Default")
      (node (ref "D1") (pin "K") (pinfunction "K_K") (pintype "passive"))
      (node (ref "R5") (pin "1") (pinfunction "1_1") (pintype "passive"))
    )
    (net (code "48") (name "Net-(D2-PadA)") (class "Default")
      (node (ref "D2") (pin "A") (pinfunction "A_A") (pintype "passive"))
      (node (ref "R2") (pin "2") (pinfunction "2_2") (pintype "passive"))
    )
    (net (code "49") (name "Net-(D3-PadA)") (class "Default")
      (node (ref "D3") (pin "A") (pinfunction "A_A") (pintype "passive"))
      (node (ref "R3") (pin "2") (pinfunction "2_2") (pintype "passive"))
    )
    (net (code "50") (name "Net-(D4-PadK)") (class "Default")
      (node (ref "D4") (pin "K") (pinfunction "K_K") (pintype "passive"))
      (node (ref "R8") (pin "1") (pinfunction "1_1") (pintype "passive"))
    )
    (net (code "51") (name "Net-(D8-PadA)") (class "Default")
      (node (ref "D8") (pin "A") (pinfunction "A_A") (pintype "passive"))
      (node (ref "R28") (pin "1") (pinfunction "1_1") (pintype "passive"))
    )
    (net (code "52") (name "Net-(D9-PadA)") (class "Default")
      (node (ref "D9") (pin "A") (pinfunction "A_A") (pintype "passive"))
      (node (ref "JK1") (pin "1") (pinfunction "1_1") (pintype "passive"))
      (node (ref "Q4") (pin "C") (pinfunction "C_C") (pintype "passive"))
    )
    (net (code "53") (name "Net-(J4-Pad1)") (class "Default")
      (node (ref "J4") (pin "1") (pinfunction "1_1") (pintype "passive"))
      (node (ref "L2") (pin "1") (pinfunction "1_1") (pintype "passive"))
    )
    (net (code "54") (name "Net-(L2-Pad2)") (class "Default")
      (node (ref "L2") (pin "2") (pinfunction "2_2") (pintype "passive"))
      (node (ref "L3") (pin "1") (pinfunction "1_1") (pintype "passive"))
    )
    (net (code "55") (name "Net-(M1-EN)") (class "Default")
      (node (ref "M1") (pin "3") (pinfunction "EN_3") (pintype "passive"))
      (node (ref "R31") (pin "2") (pinfunction "2_2") (pintype "passive"))
    )
    (net (code "56") (name "Net-(M1-RST)") (class "Default")
      (node (ref "M1") (pin "1") (pinfunction "RST_1") (pintype "passive"))
      (node (ref "R24") (pin "2") (pinfunction "2_2") (pintype "passive"))
    )
    (net (code "57") (name "Net-(OLED1-BS0)") (class "Default")
      (node (ref "OLED1") (pin "10") (pinfunction "BS0_10") (pintype "passive"))
      (node (ref "R11") (pin "1") (pinfunction "1_1") (pintype "passive"))
      (node (ref "R14") (pin "2") (pinfunction "2_2") (pintype "passive"))
    )
    (net (code "58") (name "Net-(OLED1-BS1)") (class "Default")
      (node (ref "OLED1") (pin "11") (pinfunction "BS1_11") (pintype "passive"))
      (node (ref "R15") (pin "1") (pinfunction "1_1") (pintype "passive"))
      (node (ref "R17") (pin "2") (pinfunction "2_2") (pintype "passive"))
    )
    (net (code "59") (name "Net-(OLED1-C1N)") (class "Default")
      (node (ref "C12") (pin "1") (pinfunction "1_1") (pintype "passive"))
      (node (ref "OLED1") (pin "5") (pinfunction "C1N_5") (pintype "passive"))
    )
    (net (code "60") (name "Net-(OLED1-C1P)") (class "Default")
      (node (ref "C12") (pin "2") (pinfunction "2_2") (pintype "passive"))
      (node (ref "OLED1") (pin "4") (pinfunction "C1P_4") (pintype "passive"))
    )
    (net (code "61") (name "Net-(OLED1-C2N)") (class "Default")
      (node (ref "C10") (pin "1") (pinfunction "1_1") (pintype "passive"))
      (node (ref "OLED1") (pin "3") (pinfunction "C2N_3") (pintype "passive"))
    )
    (net (code "62") (name "Net-(OLED1-C2P)") (class "Default")
      (node (ref "C10") (pin "2") (pinfunction "2_2") (pintype "passive"))
      (node (ref "OLED1") (pin "2") (pinfunction "C2P_2") (pintype "passive"))
    )
    (net (code "63") (name "Net-(OLED1-D2)") (class "Default")
      (node (ref "OLED1") (pin "20") (pinfunction "D2_20") (pintype "passive"))
      (node (ref "R34") (pin "1") (pinfunction "1_1") (pintype "passive"))
    )
    (net (code "64") (name "Net-(OLED1-IREF)") (class "Default")
      (node (ref "OLED1") (pin "26") (pinfunction "IREF_26") (pintype "passive"))
      (node (ref "R10") (pin "2") (pinfunction "2_2") (pintype "passive"))
    )
    (net (code "65") (name "Net-(OLED1-VCC)") (class "Default")
      (node (ref "C9") (pin "2") (pinfunction "2_2") (pintype "passive"))
      (node (ref "OLED1") (pin "28") (pinfunction "VCC_28") (pintype "passive"))
    )
    (net (code "66") (name "Net-(OLED1-VCOMH)") (class "Default")
      (node (ref "C11") (pin "2") (pinfunction "2_2") (pintype "passive"))
      (node (ref "OLED1") (pin "27") (pinfunction "VCOMH_27") (pintype "passive"))
    )
    (net (code "67") (name "Net-(P1-Pad3)") (class "Default")
      (node (ref "P1") (pin "3") (pinfunction "3_3") (pintype "passive"))
      (node (ref "R6") (pin "2") (pinfunction "2_2") (pintype "passive"))
    )
    (net (code "68") (name "Net-(P1-Pad4)") (class "Default")
      (node (ref "P1") (pin "4") (pinfunction "4_4") (pintype "passive"))
      (node (ref "R7") (pin "1") (pinfunction "1_1") (pintype "passive"))
    )
    (net (code "69") (name "Net-(Q1-PadG)") (class "Default")
      (node (ref "Q1") (pin "G") (pinfunction "G_G") (pintype "passive"))
      (node (ref "R12") (pin "1") (pinfunction "1_1") (pintype "passive"))
    )
    (net (code "70") (name "Net-(Q3-PadB)") (class "Default")
      (node (ref "Q3") (pin "B") (pinfunction "B_B") (pintype "passive"))
      (node (ref "R37") (pin "1") (pinfunction "1_1") (pintype "passive"))
    )
    (net (code "71") (name "Net-(Q4-PadB)") (class "Default")
      (node (ref "Q4") (pin "B") (pinfunction "B_B") (pintype "passive"))
      (node (ref "R29") (pin "1") (pinfunction "1_1") (pintype "passive"))
      (node (ref "R30") (pin "2") (pinfunction "2_2") (pintype "passive"))
    )
    (net (code "72") (name "Net-(R25-Pad1)") (class "Default")
      (node (ref "R25") (pin "1") (pinfunction "1_1") (pintype "passive"))
      (node (ref "R27") (pin "1") (pinfunction "1_1") (pintype "passive"))
      (node (ref "U6") (pin "2") (pinfunction "R_2") (pintype "passive"))
    )
    (net (code "73") (name "Net-(R25-Pad2)") (class "Default")
      (node (ref "R25") (pin "2") (pinfunction "2_2") (pintype "passive"))
      (node (ref "U6") (pin "1") (pinfunction "R_1") (pintype "passive"))
    )
    (net (code "74") (name "Net-(SW2-NO2)") (class "Default")
      (node (ref "C21") (pin "2") (pinfunction "2_2") (pintype "passive"))
      (node (ref "C22") (pin "2") (pinfunction "2_2") (pintype "passive"))
      (node (ref "L1") (pin "1") (pinfunction "1_1") (pintype "passive"))
      (node (ref "SW2") (pin "4") (pinfunction "NO2_4") (pintype "passive"))
      (node (ref "U4") (pin "4") (pinfunction "EN_4") (pintype "passive"))
      (node (ref "U4") (pin "5") (pinfunction "VCC_5") (pintype "passive"))
    )
    (net (code "75") (name "Net-(U1-CE)") (class "Default")
      (node (ref "C1") (pin "2") (pinfunction "2_2") (pintype "passive"))
      (node (ref "R1") (pin "2") (pinfunction "2_2") (pintype "passive"))
      (node (ref "R2") (pin "1") (pinfunction "1_1") (pintype "passive"))
      (node (ref "R3") (pin "1") (pinfunction "1_1") (pintype "passive"))
      (node (ref "U1") (pin "4") (pinfunction "VCC_4") (pintype "passive"))
      (node (ref "U1") (pin "8") (pinfunction "CE_8") (pintype "passive"))
    )
    (net (code "76") (name "Net-(U1-PROG)") (class "Default")
      (node (ref "R9") (pin "1") (pinfunction "1_1") (pintype "passive"))
      (node (ref "U1") (pin "2") (pinfunction "PROG_2") (pintype "passive"))
    )
    (net (code "77") (name "Net-(U1-~{CHRG})") (class "Default")
      (node (ref "D3") (pin "K") (pinfunction "K_K") (pintype "passive"))
      (node (ref "U1") (pin "7") (pinfunction "~{CHRG}_7") (pintype "passive"))
    )
    (net (code "78") (name "Net-(U1-~{STDBY})") (class "Default")
      (node (ref "D2") (pin "K") (pinfunction "K_K") (pintype "passive"))
      (node (ref "U1") (pin "6") (pinfunction "~{STDBY}_6") (pintype "passive"))
    )
    (net (code "79") (name "Net-(U2-BP)") (class "Default")
      (node (ref "C8") (pin "2") (pinfunction "2_2") (pintype "passive"))
      (node (ref "U2") (pin "4") (pinfunction "BP_4") (pintype "passive"))
    )
    (net (code "80") (name "Net-(U4-FB)") (class "Default")
      (node (ref "R18") (pin "1") (pinfunction "1_1") (pintype "passive"))
      (node (ref "R19") (pin "2") (pinfunction "2_2") (pintype "passive"))
      (node (ref "U4") (pin "3") (pinfunction "FB_3") (pintype "passive"))
    )
    (net (code "81") (name "Net-(U4-LX)") (class "Default")
      (node (ref "D7") (pin "A") (pinfunction "A_A") (pintype "passive"))
      (node (ref "L1") (pin "2") (pinfunction "2_2") (pintype "passive"))
      (node (ref "U4") (pin "1") (pinfunction "LX_1") (pintype "passive"))
    )
    (net (code "82") (name "Net-(U4-OC)") (class "Default")
      (node (ref "R16") (pin "2") (pinfunction "2_2") (pintype "passive"))
      (node (ref "U4") (pin "6") (pinfunction "OC_6") (pintype "passive"))
    )
    (net (code "83") (name "Net-(U5-Con)") (class "Default")
      (node (ref "C31") (pin "1") (pinfunction "1_1") (pintype "passive"))
      (node (ref "R26") (pin "2") (pinfunction "2_2") (pintype "passive"))
      (node (ref "U5") (pin "Hole") (pinfunction "Con_Hole") (pintype "passive"))
      (node (ref "U6") (pin "8") (pinfunction "N/F_8") (pintype "passive"))
    )
    (net (code "84") (name "Net-(U6-LED)") (class "Default")
      (node (ref "R28") (pin "2") (pinfunction "2_2") (pintype "passive"))
      (node (ref "U6") (pin "6") (pinfunction "LED_6") (pintype "passive"))
    )
    (net (code "85") (name "Net-(U6-VDD)") (class "Default")
      (node (ref "C32") (pin "2") (pinfunction "2_2") (pintype "passive"))
      (node (ref "C33") (pin "2") (pinfunction "2_2") (pintype "passive"))
      (node (ref "J4") (pin "2") (pinfunction "2_2") (pintype "passive"))
      (node (ref "JK1") (pin "4") (pinfunction "4_4") (pintype "passive"))
      (node (ref "L3") (pin "3") (pinfunction "3_3") (pintype "passive"))
      (node (ref "R27") (pin "2") (pinfunction "2_2") (pintype "passive"))
      (node (ref "U6") (pin "7") (pinfunction "VDD_7") (pintype "passive"))
    )
    (net (code "86") (name "Net-(U6-VIN)") (class "Default")
      (node (ref "C33") (pin "1") (pinfunction "1_1") (pintype "passive"))
      (node (ref "L3") (pin "2") (pinfunction "2_2") (pintype "passive"))
      (node (ref "U6") (pin "5") (pinfunction "VIN_5") (pintype "passive"))
    )
    (net (code "87") (name "Net-(USB1-D+)") (class "Default")
      (node (ref "R21") (pin "1") (pinfunction "1_1") (pintype "passive"))
      (node (ref "USB1") (pin "3") (pinfunction "D+_3") (pintype "passive"))
    )
    (net (code "88") (name "Net-(USB1-D-)") (class "Default")
      (node (ref "R20") (pin "1") (pinfunction "1_1") (pintype "passive"))
      (node (ref "USB1") (pin "2") (pinfunction "D-_2") (pintype "passive"))
    )
    (net (code "89") (name "VBAT3.7") (class "Default")
      (node (ref "C3") (pin "1") (pinfunction "1_1") (pintype "passive"))
      (node (ref "J2") (pin "1") (pinfunction "1_1") (pintype "passive"))
      (node (ref "SW2") (pin "5") (pinfunction "COM2_5") (pintype "passive"))
      (node (ref "U1") (pin "5") (pinfunction "BAT_5") (pintype "passive"))
    )
    (net (code "90") (name "VBUS") (class "Default")
      (node (ref "D5") (pin "A") (pinfunction "A_A") (pintype "passive"))
      (node (ref "R1") (pin "1") (pinfunction "1_1") (pintype "passive"))
      (node (ref "R12") (pin "2") (pinfunction "2_2") (pintype "passive"))
      (node (ref "R13") (pin "2") (pinfunction "2_2") (pintype "passive"))
      (node (ref "USB1") (pin "1") (pinfunction "+_1") (pintype "passive"))
    )
    (net (code "91") (name "VCC3V3") (class "Default")
      (node (ref "B1") (pin "1") (pinfunction "1_1") (pintype "passive"))
      (node (ref "C16") (pin "1") (pinfunction "1_1") (pintype "passive"))
      (node (ref "C25") (pin "2") (pinfunction "2_2") (pintype "passive"))
      (node (ref "C26") (pin "2") (pinfunction "2_2") (pintype "passive"))
      (node (ref "C27") (pin "2") (pinfunction "2_2") (pintype "passive"))
      (node (ref "C28") (pin "2") (pinfunction "2_2") (pintype "passive"))
      (node (ref "C4") (pin "2") (pinfunction "2_2") (pintype "passive"))
      (node (ref "C5") (pin "2") (pinfunction "2_2") (pintype "passive"))
      (node (ref "C6") (pin "2") (pinfunction "2_2") (pintype "passive"))
      (node (ref "D1") (pin "A") (pinfunction "A_A") (pintype "passive"))
      (node (ref "D4") (pin "A") (pinfunction "A_A") (pintype "passive"))
      (node (ref "J1") (pin "5") (pinfunction "5_5") (pintype "passive"))
      (node (ref "J3") (pin "2") (pinfunction "2_2") (pintype "passive"))
      (node (ref "M1") (pin "8") (pinfunction "VCC_8") (pintype "passive"))
      (node (ref "P1") (pin "1") (pinfunction "1_1") (pintype "passive"))
      (node (ref "P1") (pin "2") (pinfunction "2_2") (pintype "passive"))
      (node (ref "P2") (pin "4") (pinfunction "4_4") (pintype "passive"))
      (node (ref "P3") (pin "18") (pinfunction "18_18") (pintype "passive"))
      (node (ref "P4") (pin "1") (pinfunction "1_1") (pintype "passive"))
      (node (ref "Q2") (pin "3") (pinfunction "VIN_3") (pintype "passive"))
      (node (ref "R24") (pin "1") (pinfunction "1_1") (pintype "passive"))
      (node (ref "R31") (pin "1") (pinfunction "1_1") (pintype "passive"))
      (node (ref "R35") (pin "1") (pinfunction "1_1") (pintype "passive"))
      (node (ref "R4") (pin "1") (pinfunction "1_1") (pintype "passive"))
      (node (ref "U2") (pin "5") (pinfunction "VOUT_5") (pintype "power_in"))
      (node (ref "U3") (pin "24") (pinfunction "VDD_1_24") (pintype "passive"))
      (node (ref "U3") (pin "36") (pinfunction "VDD_2_36") (pintype "passive"))
      (node (ref "U3") (pin "48") (pinfunction "VDD_3_48") (pintype "passive"))
      (node (ref "U3") (pin "9") (pinfunction "VDDA_9") (pintype "passive"))
    )
    (net (code "92") (name "VCC5V") (class "Default")
      (node (ref "C7") (pin "2") (pinfunction "2_2") (pintype "passive"))
      (node (ref "D9") (pin "K") (pinfunction "K_K") (pintype "passive"))
      (node (ref "J5") (pin "4") (pinfunction "4_4") (pintype "passive"))
      (node (ref "JK1") (pin "2") (pinfunction "2_2") (pintype "passive"))
      (node (ref "JK1") (pin "3") (pinfunction "3_3") (pintype "passive"))
      (node (ref "P4") (pin "3") (pinfunction "3_3") (pintype "passive"))
      (node (ref "R22") (pin "1") (pinfunction "1_1") (pintype "passive"))
      (node (ref "SW2") (pin "3") (pinfunction "NO1_3") (pintype "passive"))
      (node (ref "U2") (pin "1") (pinfunction "VIN_1") (pintype "power_in"))
      (node (ref "U2") (pin "3") (pinfunction "EN_3") (pintype "input"))
    )
    (net (code "93") (name "unconnected-(J5-Pad5)") (class "Default")
      (node (ref "J5") (pin "5") (pinfunction "5_5") (pintype "passive"))
    )
    (net (code "94") (name "unconnected-(M1-ADC-Pad2)") (class "Default")
      (node (ref "M1") (pin "2") (pinfunction "ADC_2") (pintype "passive"))
    )
    (net (code "95") (name "unconnected-(M1-CS0-Pad9)") (class "Default")
      (node (ref "M1") (pin "9") (pinfunction "CS0_9") (pintype "passive"))
    )
    (net (code "96") (name "unconnected-(M1-GPIO0-Pad18)") (class "Default")
      (node (ref "M1") (pin "18") (pinfunction "GPIO0_18") (pintype "passive"))
    )
    (net (code "97") (name "unconnected-(M1-GPIO2-Pad17)") (class "Default")
      (node (ref "M1") (pin "17") (pinfunction "GPIO2_17") (pintype "passive"))
    )
    (net (code "98") (name "unconnected-(M1-GPIO9-Pad11)") (class "Default")
      (node (ref "M1") (pin "11") (pinfunction "GPIO9_11") (pintype "passive"))
    )
    (net (code "99") (name "unconnected-(M1-GPIO10-Pad12)") (class "Default")
      (node (ref "M1") (pin "12") (pinfunction "GPIO10_12") (pintype "passive"))
    )
    (net (code "100") (name "unconnected-(M1-GPIO12-Pad6)") (class "Default")
      (node (ref "M1") (pin "6") (pinfunction "GPIO12_6") (pintype "passive"))
    )
    (net (code "101") (name "unconnected-(M1-GPIO13-Pad7)") (class "Default")
      (node (ref "M1") (pin "7") (pinfunction "GPIO13_7") (pintype "passive"))
    )
    (net (code "102") (name "unconnected-(M1-GPIO14-Pad5)") (class "Default")
      (node (ref "M1") (pin "5") (pinfunction "GPIO14_5") (pintype "passive"))
    )
    (net (code "103") (name "unconnected-(M1-GPIO16-Pad4)") (class "Default")
      (node (ref "M1") (pin "4") (pinfunction "GPIO16_4") (pintype "passive"))
    )
    (net (code "104") (name "unconnected-(M1-MISO-Pad10)") (class "Default")
      (node (ref "M1") (pin "10") (pinfunction "MISO_10") (pintype "passive"))
    )
    (net (code "105") (name "unconnected-(M1-MOSI-Pad13)") (class "Default")
      (node (ref "M1") (pin "13") (pinfunction "MOSI_13") (pintype "passive"))
    )
    (net (code "106") (name "unconnected-(M1-RXD0-Pad21)") (class "Default")
      (node (ref "M1") (pin "21") (pinfunction "RXD0_21") (pintype "passive"))
    )
    (net (code "107") (name "unconnected-(M1-SCLK-Pad14)") (class "Default")
      (node (ref "M1") (pin "14") (pinfunction "SCLK_14") (pintype "passive"))
    )
    (net (code "108") (name "unconnected-(M1-TXD0-Pad22)") (class "Default")
      (node (ref "M1") (pin "22") (pinfunction "TXD0_22") (pintype "passive"))
    )
    (net (code "109") (name "unconnected-(SW2-NC1-Pad1)") (class "Default")
      (node (ref "SW2") (pin "1") (pinfunction "NC1_1") (pintype "passive"))
    )
    (net (code "110") (name "unconnected-(SW2-NC2-Pad6)") (class "Default")
      (node (ref "SW2") (pin "6") (pinfunction "NC2_6") (pintype "passive"))
    )
  )
)
